# DRV8711.net
KiCad netlist of a schematic drawn in EAGLE
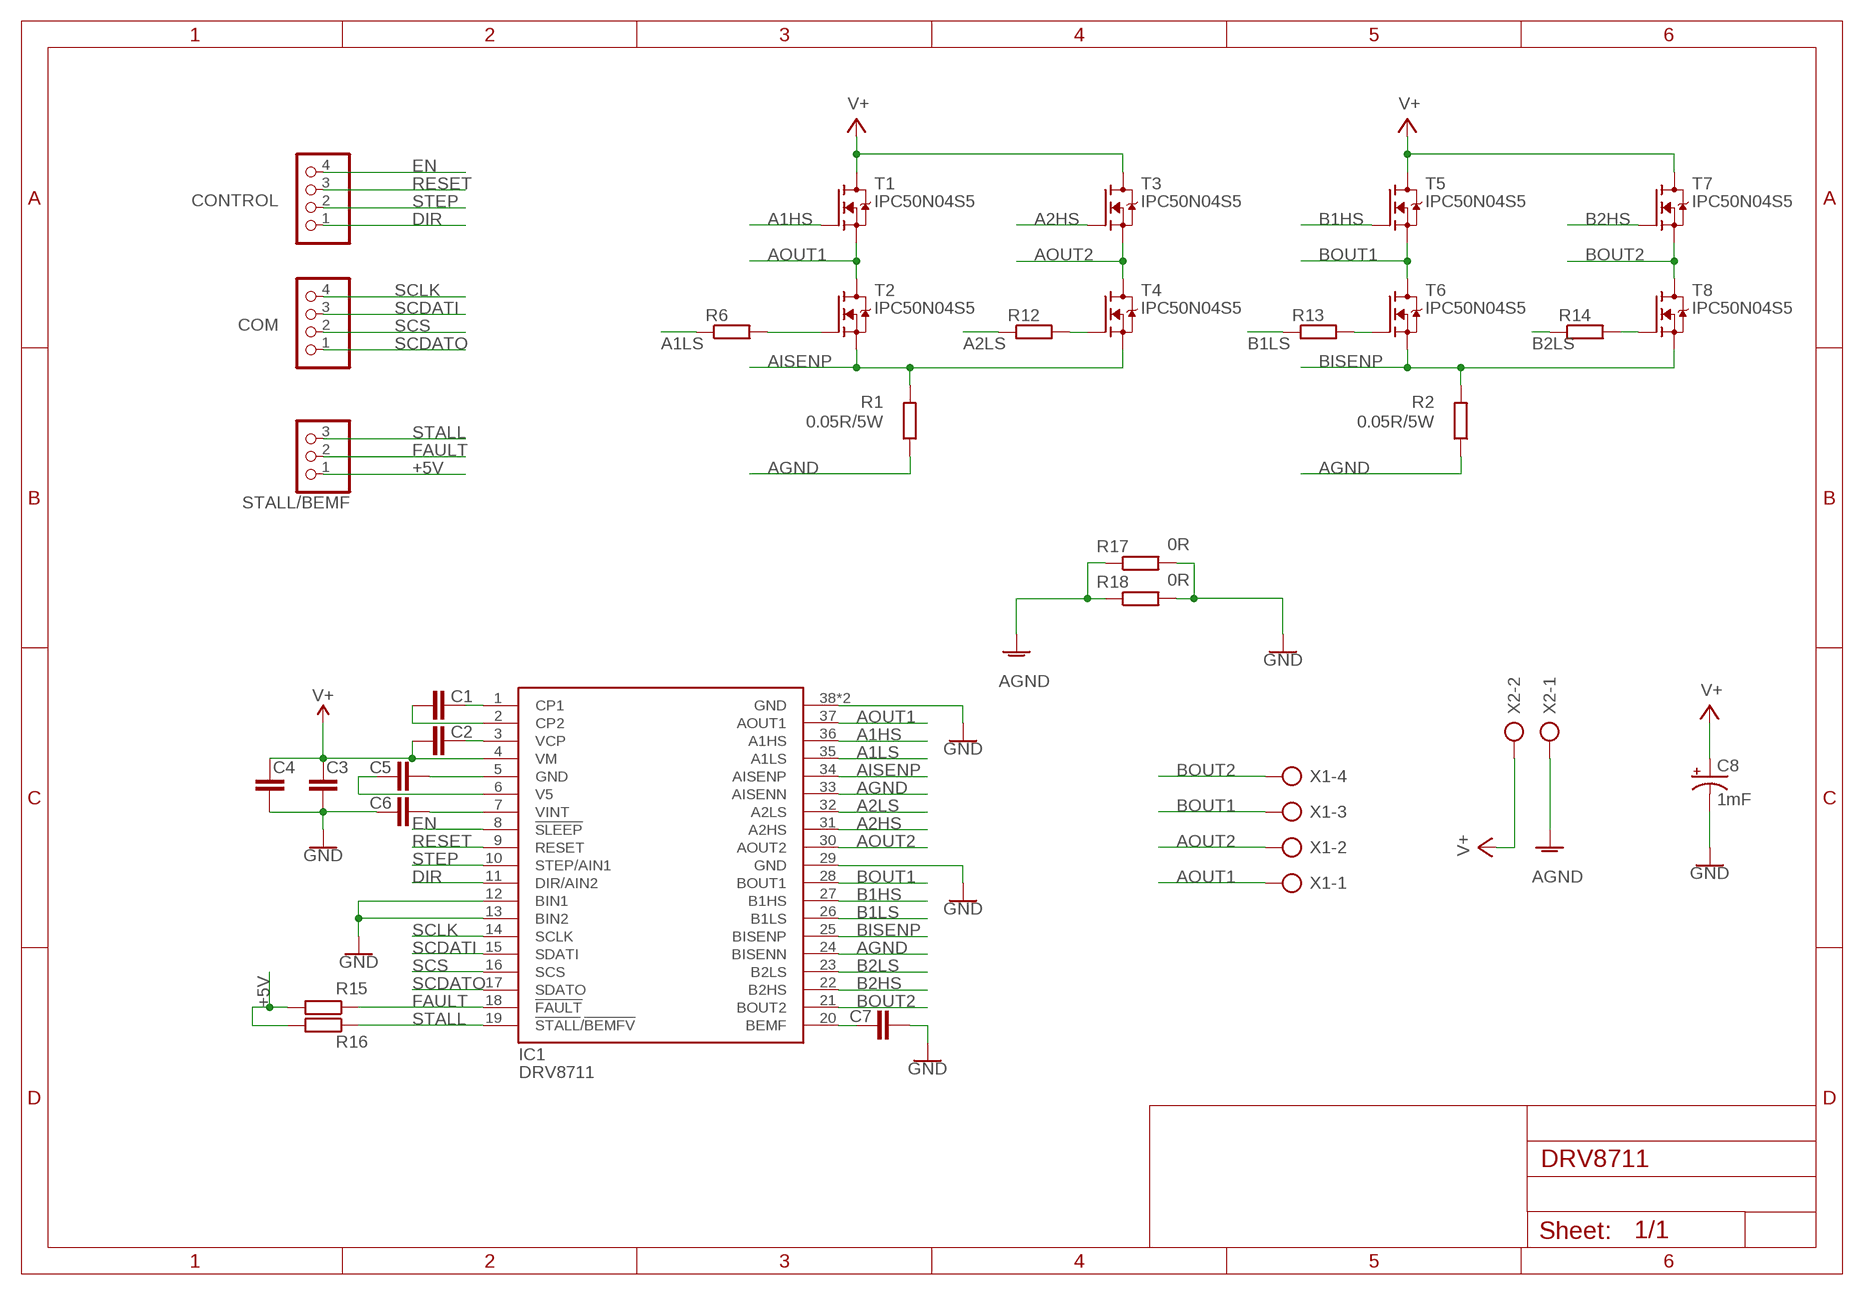
[diagram p0: schematic, sheet 1]

(export (version "E")
  (design (tool "Eeschema 10.0.6"))
  (components
    (comp (ref "C1")
      (value "C-EUC0805")
      (footprint "eagle-import:C0805")
      (libsource (lib "eagle-import") (part "C-EUC0805"))
    )
    (comp (ref "C2")
      (value "C-EUC0805")
      (footprint "eagle-import:C0805")
      (libsource (lib "eagle-import") (part "C-EUC0805"))
    )
    (comp (ref "C3")
      (value "C-EUC0805")
      (footprint "eagle-import:C0805")
      (libsource (lib "eagle-import") (part "C-EUC0805"))
    )
    (comp (ref "C4")
      (value "C-EUC0805")
      (footprint "eagle-import:C0805")
      (libsource (lib "eagle-import") (part "C-EUC0805"))
    )
    (comp (ref "C5")
      (value "C-EUC0805")
      (footprint "eagle-import:C0805")
      (libsource (lib "eagle-import") (part "C-EUC0805"))
    )
    (comp (ref "C6")
      (value "C-EUC0805")
      (footprint "eagle-import:C0805")
      (libsource (lib "eagle-import") (part "C-EUC0805"))
    )
    (comp (ref "C7")
      (value "C-EUC0805")
      (footprint "eagle-import:C0805")
      (libsource (lib "eagle-import") (part "C-EUC0805"))
    )
    (comp (ref "C8")
      (value "1mF")
      (footprint "eagle-import:CPOL-RADIAL-5MM-10MM")
      (libsource (lib "eagle-import") (part "1000UF-RADIAL-5MM-25V-20%"))
    )
    (comp (ref "COM")
      (value "PINHD-1X4")
      (footprint "eagle-import:1X04")
      (libsource (lib "eagle-import") (part "PINHD-1X4"))
    )
    (comp (ref "CONTROL")
      (value "PINHD-1X4")
      (footprint "eagle-import:1X04")
      (libsource (lib "eagle-import") (part "PINHD-1X4"))
    )
    (comp (ref "IC1")
      (value "DRV8711")
      (footprint "eagle-import:R-PDSO-G38")
      (libsource (lib "eagle-import") (part "DRV8711"))
    )
    (comp (ref "R1")
      (value "0.05R/5W")
      (footprint "eagle-import:R4527")
      (libsource (lib "eagle-import") (part "R-EU_R4527"))
    )
    (comp (ref "R2")
      (value "0.05R/5W")
      (footprint "eagle-import:R4527")
      (libsource (lib "eagle-import") (part "R-EU_R4527"))
    )
    (comp (ref "R6")
      (value "R-EU_R0805")
      (footprint "eagle-import:R0805")
      (libsource (lib "eagle-import") (part "R-EU_R0805"))
    )
    (comp (ref "R12")
      (value "R-EU_R0805")
      (footprint "eagle-import:R0805")
      (libsource (lib "eagle-import") (part "R-EU_R0805"))
    )
    (comp (ref "R13")
      (value "R-EU_R0805")
      (footprint "eagle-import:R0805")
      (libsource (lib "eagle-import") (part "R-EU_R0805"))
    )
    (comp (ref "R14")
      (value "R-EU_R0805")
      (footprint "eagle-import:R0805")
      (libsource (lib "eagle-import") (part "R-EU_R0805"))
    )
    (comp (ref "R15")
      (value "R-EU_R0805")
      (footprint "eagle-import:R0805")
      (libsource (lib "eagle-import") (part "R-EU_R0805"))
    )
    (comp (ref "R16")
      (value "R-EU_R0805")
      (footprint "eagle-import:R0805")
      (libsource (lib "eagle-import") (part "R-EU_R0805"))
    )
    (comp (ref "R17")
      (value "0R")
      (footprint "eagle-import:R0805")
      (libsource (lib "eagle-import") (part "R-EU_R0805"))
    )
    (comp (ref "R18")
      (value "0R")
      (footprint "eagle-import:R0805")
      (libsource (lib "eagle-import") (part "R-EU_R0805"))
    )
    (comp (ref "STALL/BEMF")
      (value "PINHD-1X3")
      (footprint "eagle-import:1X03")
      (libsource (lib "eagle-import") (part "PINHD-1X3"))
    )
    (comp (ref "T1")
      (value "IPC50N04S5")
      (footprint "eagle-import:PG-TDSON-8-33")
      (libsource (lib "eagle-import") (part "IPC50N04S5"))
    )
    (comp (ref "T2")
      (value "IPC50N04S5")
      (footprint "eagle-import:PG-TDSON-8-33")
      (libsource (lib "eagle-import") (part "IPC50N04S5"))
    )
    (comp (ref "T3")
      (value "IPC50N04S5")
      (footprint "eagle-import:PG-TDSON-8-33")
      (libsource (lib "eagle-import") (part "IPC50N04S5"))
    )
    (comp (ref "T4")
      (value "IPC50N04S5")
      (footprint "eagle-import:PG-TDSON-8-33")
      (libsource (lib "eagle-import") (part "IPC50N04S5"))
    )
    (comp (ref "T5")
      (value "IPC50N04S5")
      (footprint "eagle-import:PG-TDSON-8-33")
      (libsource (lib "eagle-import") (part "IPC50N04S5"))
    )
    (comp (ref "T6")
      (value "IPC50N04S5")
      (footprint "eagle-import:PG-TDSON-8-33")
      (libsource (lib "eagle-import") (part "IPC50N04S5"))
    )
    (comp (ref "T7")
      (value "IPC50N04S5")
      (footprint "eagle-import:PG-TDSON-8-33")
      (libsource (lib "eagle-import") (part "IPC50N04S5"))
    )
    (comp (ref "T8")
      (value "IPC50N04S5")
      (footprint "eagle-import:PG-TDSON-8-33")
      (libsource (lib "eagle-import") (part "IPC50N04S5"))
    )
    (comp (ref "X1")
      (value "AK500/4")
      (footprint "eagle-import:AK500_4")
      (libsource (lib "eagle-import") (part "AK500/4"))
    )
    (comp (ref "X2")
      (value "AK500/2")
      (footprint "eagle-import:AK500_2")
      (libsource (lib "eagle-import") (part "AK500/2"))
    )
  )
  (nets
    (net (code "1") (name "/+5V") (class "Default")
      (node (ref "R15") (pin "2") (pinfunction "2_2") (pintype "passive"))
      (node (ref "R16") (pin "2") (pinfunction "2_2") (pintype "passive"))
      (node (ref "STALL/BEMF") (pin "1") (pinfunction "1_1") (pintype "passive"))
    )
    (net (code "2") (name "/A1HS") (class "Default")
      (node (ref "IC1") (pin "36") (pinfunction "A1HS_36") (pintype "bidirectional"))
      (node (ref "T1") (pin "3") (pinfunction "G_3") (pintype "passive"))
    )
    (net (code "3") (name "/A1LS") (class "Default")
      (node (ref "IC1") (pin "35") (pinfunction "A1LS_35") (pintype "bidirectional"))
      (node (ref "R6") (pin "1") (pinfunction "1_1") (pintype "passive"))
    )
    (net (code "4") (name "/A2HS") (class "Default")
      (node (ref "IC1") (pin "31") (pinfunction "A2HS_31") (pintype "bidirectional"))
      (node (ref "T3") (pin "3") (pinfunction "G_3") (pintype "passive"))
    )
    (net (code "5") (name "/A2LS") (class "Default")
      (node (ref "IC1") (pin "32") (pinfunction "A2LS_32") (pintype "bidirectional"))
      (node (ref "R12") (pin "1") (pinfunction "1_1") (pintype "passive"))
    )
    (net (code "6") (name "/AISENP") (class "Default")
      (node (ref "IC1") (pin "34") (pinfunction "AISENP_34") (pintype "bidirectional"))
      (node (ref "R1") (pin "2") (pinfunction "2_2") (pintype "passive"))
      (node (ref "T2") (pin "2") (pinfunction "S_2") (pintype "passive"))
      (node (ref "T4") (pin "2") (pinfunction "S_2") (pintype "passive"))
    )
    (net (code "7") (name "/AOUT1") (class "Default")
      (node (ref "IC1") (pin "37") (pinfunction "AOUT1_37") (pintype "bidirectional"))
      (node (ref "T1") (pin "2") (pinfunction "S_2") (pintype "passive"))
      (node (ref "T2") (pin "1") (pinfunction "D_1") (pintype "passive"))
      (node (ref "X1") (pin "1") (pinfunction "KL_1") (pintype "passive"))
    )
    (net (code "8") (name "/AOUT2") (class "Default")
      (node (ref "IC1") (pin "30") (pinfunction "AOUT2_30") (pintype "bidirectional"))
      (node (ref "T3") (pin "2") (pinfunction "S_2") (pintype "passive"))
      (node (ref "T4") (pin "1") (pinfunction "D_1") (pintype "passive"))
      (node (ref "X1") (pin "2") (pinfunction "KL_2") (pintype "passive"))
    )
    (net (code "9") (name "/B1HS") (class "Default")
      (node (ref "IC1") (pin "27") (pinfunction "B1HS_27") (pintype "bidirectional"))
      (node (ref "T5") (pin "3") (pinfunction "G_3") (pintype "passive"))
    )
    (net (code "10") (name "/B1LS") (class "Default")
      (node (ref "IC1") (pin "26") (pinfunction "B1LS_26") (pintype "bidirectional"))
      (node (ref "R13") (pin "1") (pinfunction "1_1") (pintype "passive"))
    )
    (net (code "11") (name "/B2HS") (class "Default")
      (node (ref "IC1") (pin "22") (pinfunction "B2HS_22") (pintype "bidirectional"))
      (node (ref "T7") (pin "3") (pinfunction "G_3") (pintype "passive"))
    )
    (net (code "12") (name "/B2LS") (class "Default")
      (node (ref "IC1") (pin "23") (pinfunction "B2LS_23") (pintype "bidirectional"))
      (node (ref "R14") (pin "1") (pinfunction "1_1") (pintype "passive"))
    )
    (net (code "13") (name "/BISENP") (class "Default")
      (node (ref "IC1") (pin "25") (pinfunction "BISENP_25") (pintype "bidirectional"))
      (node (ref "R2") (pin "2") (pinfunction "2_2") (pintype "passive"))
      (node (ref "T6") (pin "2") (pinfunction "S_2") (pintype "passive"))
      (node (ref "T8") (pin "2") (pinfunction "S_2") (pintype "passive"))
    )
    (net (code "14") (name "/BOUT1") (class "Default")
      (node (ref "IC1") (pin "28") (pinfunction "BOUT1_28") (pintype "bidirectional"))
      (node (ref "T5") (pin "2") (pinfunction "S_2") (pintype "passive"))
      (node (ref "T6") (pin "1") (pinfunction "D_1") (pintype "passive"))
      (node (ref "X1") (pin "3") (pinfunction "KL_3") (pintype "passive"))
    )
    (net (code "15") (name "/BOUT2") (class "Default")
      (node (ref "IC1") (pin "21") (pinfunction "BOUT2_21") (pintype "bidirectional"))
      (node (ref "T7") (pin "2") (pinfunction "S_2") (pintype "passive"))
      (node (ref "T8") (pin "1") (pinfunction "D_1") (pintype "passive"))
      (node (ref "X1") (pin "4") (pinfunction "KL_4") (pintype "passive"))
    )
    (net (code "16") (name "/DIR") (class "Default")
      (node (ref "CONTROL") (pin "1") (pinfunction "1_1") (pintype "passive"))
      (node (ref "IC1") (pin "11") (pinfunction "DIR/AIN2_11") (pintype "bidirectional"))
    )
    (net (code "17") (name "/EN") (class "Default")
      (node (ref "CONTROL") (pin "4") (pinfunction "4_4") (pintype "passive"))
      (node (ref "IC1") (pin "8") (pinfunction "~{SLEEP}_8") (pintype "bidirectional"))
    )
    (net (code "18") (name "/FAULT") (class "Default")
      (node (ref "IC1") (pin "18") (pinfunction "~{FAULT}_18") (pintype "bidirectional"))
      (node (ref "R15") (pin "1") (pinfunction "1_1") (pintype "passive"))
      (node (ref "STALL/BEMF") (pin "2") (pinfunction "2_2") (pintype "passive"))
    )
    (net (code "19") (name "/RESET") (class "Default")
      (node (ref "CONTROL") (pin "3") (pinfunction "3_3") (pintype "passive"))
      (node (ref "IC1") (pin "9") (pinfunction "RESET_9") (pintype "bidirectional"))
    )
    (net (code "20") (name "/SCDATI") (class "Default")
      (node (ref "COM") (pin "3") (pinfunction "3_3") (pintype "passive"))
      (node (ref "IC1") (pin "15") (pinfunction "SDATI_15") (pintype "bidirectional"))
    )
    (net (code "21") (name "/SCDATO") (class "Default")
      (node (ref "COM") (pin "1") (pinfunction "1_1") (pintype "passive"))
      (node (ref "IC1") (pin "17") (pinfunction "SDATO_17") (pintype "bidirectional"))
    )
    (net (code "22") (name "/SCLK") (class "Default")
      (node (ref "COM") (pin "4") (pinfunction "4_4") (pintype "passive"))
      (node (ref "IC1") (pin "14") (pinfunction "SCLK_14") (pintype "bidirectional"))
    )
    (net (code "23") (name "/SCS") (class "Default")
      (node (ref "COM") (pin "2") (pinfunction "2_2") (pintype "passive"))
      (node (ref "IC1") (pin "16") (pinfunction "SCS_16") (pintype "bidirectional"))
    )
    (net (code "24") (name "/STALL") (class "Default")
      (node (ref "IC1") (pin "19") (pinfunction "~{STALL}/~{BEMFV}_19") (pintype "bidirectional"))
      (node (ref "R16") (pin "1") (pinfunction "1_1") (pintype "passive"))
      (node (ref "STALL/BEMF") (pin "3") (pinfunction "3_3") (pintype "passive"))
    )
    (net (code "25") (name "/STEP") (class "Default")
      (node (ref "CONTROL") (pin "2") (pinfunction "2_2") (pintype "passive"))
      (node (ref "IC1") (pin "10") (pinfunction "STEP/AIN1_10") (pintype "bidirectional"))
    )
    (net (code "26") (name "AGND") (class "Default")
      (node (ref "IC1") (pin "24") (pinfunction "BISENN_24") (pintype "bidirectional"))
      (node (ref "IC1") (pin "33") (pinfunction "AISENN_33") (pintype "bidirectional"))
      (node (ref "R1") (pin "1") (pinfunction "1_1") (pintype "passive"))
      (node (ref "R17") (pin "1") (pinfunction "1_1") (pintype "passive"))
      (node (ref "R18") (pin "1") (pinfunction "1_1") (pintype "passive"))
      (node (ref "R2") (pin "1") (pinfunction "1_1") (pintype "passive"))
      (node (ref "X2") (pin "1") (pinfunction "KL_1") (pintype "passive"))
    )
    (net (code "27") (name "GND") (class "Default")
      (node (ref "C3") (pin "1") (pinfunction "1_1") (pintype "passive"))
      (node (ref "C4") (pin "1") (pinfunction "1_1") (pintype "passive"))
      (node (ref "C5") (pin "1") (pinfunction "1_1") (pintype "passive"))
      (node (ref "C6") (pin "2") (pinfunction "2_2") (pintype "passive"))
      (node (ref "C7") (pin "1") (pinfunction "1_1") (pintype "passive"))
      (node (ref "C8") (pin "-") (pinfunction "-_-") (pintype "passive"))
      (node (ref "IC1") (pin "12") (pinfunction "BIN1_12") (pintype "bidirectional"))
      (node (ref "IC1") (pin "13") (pinfunction "BIN2_13") (pintype "bidirectional"))
      (node (ref "IC1") (pin "29") (pinfunction "GND_29") (pintype "bidirectional"))
      (node (ref "IC1") (pin "38") (pinfunction "GND_38") (pintype "bidirectional"))
      (node (ref "IC1") (pin "5") (pinfunction "GND_5") (pintype "bidirectional"))
      (node (ref "IC1") (pin "PAD") (pinfunction "GND_PAD") (pintype "bidirectional"))
      (node (ref "R17") (pin "2") (pinfunction "2_2") (pintype "passive"))
      (node (ref "R18") (pin "2") (pinfunction "2_2") (pintype "passive"))
    )
    (net (code "28") (name "Net-(IC1-BEMF)") (class "Default")
      (node (ref "C7") (pin "2") (pinfunction "2_2") (pintype "passive"))
      (node (ref "IC1") (pin "20") (pinfunction "BEMF_20") (pintype "bidirectional"))
    )
    (net (code "29") (name "Net-(IC1-CP1)") (class "Default")
      (node (ref "C1") (pin "2") (pinfunction "2_2") (pintype "passive"))
      (node (ref "IC1") (pin "1") (pinfunction "CP1_1") (pintype "bidirectional"))
    )
    (net (code "30") (name "Net-(IC1-CP2)") (class "Default")
      (node (ref "C1") (pin "1") (pinfunction "1_1") (pintype "passive"))
      (node (ref "IC1") (pin "2") (pinfunction "CP2_2") (pintype "bidirectional"))
    )
    (net (code "31") (name "Net-(IC1-V5)") (class "Default")
      (node (ref "C5") (pin "2") (pinfunction "2_2") (pintype "passive"))
      (node (ref "IC1") (pin "6") (pinfunction "V5_6") (pintype "bidirectional"))
    )
    (net (code "32") (name "Net-(IC1-VCP)") (class "Default")
      (node (ref "C2") (pin "2") (pinfunction "2_2") (pintype "passive"))
      (node (ref "IC1") (pin "3") (pinfunction "VCP_3") (pintype "bidirectional"))
    )
    (net (code "33") (name "Net-(IC1-VINT)") (class "Default")
      (node (ref "C6") (pin "1") (pinfunction "1_1") (pintype "passive"))
      (node (ref "IC1") (pin "7") (pinfunction "VINT_7") (pintype "bidirectional"))
    )
    (net (code "34") (name "Net-(T2-G)") (class "Default")
      (node (ref "R6") (pin "2") (pinfunction "2_2") (pintype "passive"))
      (node (ref "T2") (pin "3") (pinfunction "G_3") (pintype "passive"))
    )
    (net (code "35") (name "Net-(T4-G)") (class "Default")
      (node (ref "R12") (pin "2") (pinfunction "2_2") (pintype "passive"))
      (node (ref "T4") (pin "3") (pinfunction "G_3") (pintype "passive"))
    )
    (net (code "36") (name "Net-(T6-G)") (class "Default")
      (node (ref "R13") (pin "2") (pinfunction "2_2") (pintype "passive"))
      (node (ref "T6") (pin "3") (pinfunction "G_3") (pintype "passive"))
    )
    (net (code "37") (name "Net-(T8-G)") (class "Default")
      (node (ref "R14") (pin "2") (pinfunction "2_2") (pintype "passive"))
      (node (ref "T8") (pin "3") (pinfunction "G_3") (pintype "passive"))
    )
    (net (code "38") (name "V+") (class "Default")
      (node (ref "C2") (pin "1") (pinfunction "1_1") (pintype "passive"))
      (node (ref "C3") (pin "2") (pinfunction "2_2") (pintype "passive"))
      (node (ref "C4") (pin "2") (pinfunction "2_2") (pintype "passive"))
      (node (ref "C8") (pin "+") (pinfunction "+_+") (pintype "passive"))
      (node (ref "IC1") (pin "4") (pinfunction "VM_4") (pintype "bidirectional"))
      (node (ref "T1") (pin "1") (pinfunction "D_1") (pintype "passive"))
      (node (ref "T3") (pin "1") (pinfunction "D_1") (pintype "passive"))
      (node (ref "T5") (pin "1") (pinfunction "D_1") (pintype "passive"))
      (node (ref "T7") (pin "1") (pinfunction "D_1") (pintype "passive"))
      (node (ref "X2") (pin "2") (pinfunction "KL_2") (pintype "passive"))
    )
  )
)
